# Sonar_Power_Schematic.net
KiCad netlist of a schematic drawn in EAGLE
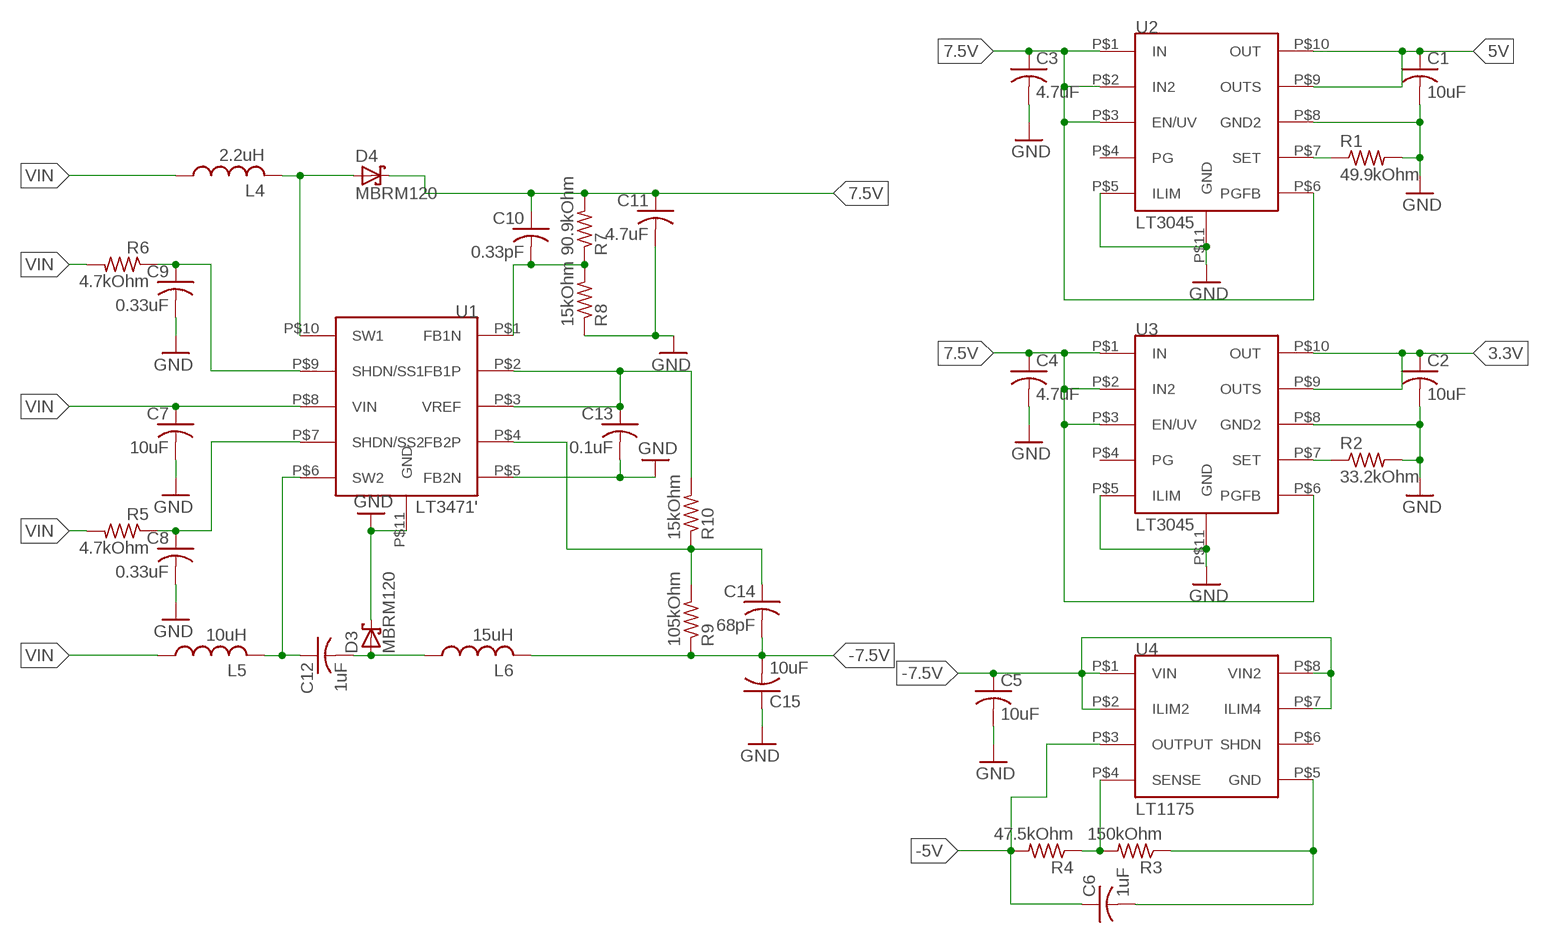
[diagram p0: schematic, sheet 1]

(export (version "E")
  (design (tool "Eeschema 10.0.6"))
  (components
    (comp (ref "C1")
      (value "10uF")
      (footprint "eagle-import:C1206K")
      (libsource (lib "eagle-import") (part "C-USC1206K"))
    )
    (comp (ref "C2")
      (value "10uF")
      (footprint "eagle-import:C1206K")
      (libsource (lib "eagle-import") (part "C-USC1206K"))
    )
    (comp (ref "C3")
      (value "4.7uF")
      (footprint "eagle-import:C0603")
      (libsource (lib "eagle-import") (part "C-USC0603"))
    )
    (comp (ref "C4")
      (value "4.7uF")
      (footprint "eagle-import:C0603")
      (libsource (lib "eagle-import") (part "C-USC0603"))
    )
    (comp (ref "C5")
      (value "10uF")
      (footprint "eagle-import:C0603")
      (libsource (lib "eagle-import") (part "C-USC0603"))
    )
    (comp (ref "C6")
      (value "1uF")
      (footprint "eagle-import:C0603")
      (libsource (lib "eagle-import") (part "C-USC0603"))
    )
    (comp (ref "C7")
      (value "10uF")
      (footprint "eagle-import:C0603")
      (libsource (lib "eagle-import") (part "C-USC0603"))
    )
    (comp (ref "C8")
      (value "0.33uF")
      (footprint "eagle-import:C0603")
      (libsource (lib "eagle-import") (part "C-USC0603"))
    )
    (comp (ref "C9")
      (value "0.33uF")
      (footprint "eagle-import:C0603")
      (libsource (lib "eagle-import") (part "C-USC0603"))
    )
    (comp (ref "C10")
      (value "0.33pF")
      (footprint "eagle-import:C0603")
      (libsource (lib "eagle-import") (part "C-USC0603"))
    )
    (comp (ref "C11")
      (value "4.7uF")
      (footprint "eagle-import:C0603")
      (libsource (lib "eagle-import") (part "C-USC0603"))
    )
    (comp (ref "C12")
      (value "1uF")
      (footprint "eagle-import:C0603")
      (libsource (lib "eagle-import") (part "C-USC0603"))
    )
    (comp (ref "C13")
      (value "0.1uF")
      (footprint "eagle-import:C0603")
      (libsource (lib "eagle-import") (part "C-USC0603"))
    )
    (comp (ref "C14")
      (value "68pF")
      (footprint "eagle-import:C0603")
      (libsource (lib "eagle-import") (part "C-USC0603"))
    )
    (comp (ref "C15")
      (value "10uF")
      (footprint "eagle-import:C0603")
      (libsource (lib "eagle-import") (part "C-USC0603"))
    )
    (comp (ref "D3")
      (value "MBRM120")
      (footprint "eagle-import:DO-216AA")
      (libsource (lib "eagle-import") (part "MBRM120"))
    )
    (comp (ref "D4")
      (value "MBRM120")
      (footprint "eagle-import:DO-216AA")
      (libsource (lib "eagle-import") (part "MBRM120"))
    )
    (comp (ref "L4")
      (value "2.2uH")
      (footprint "eagle-import:NS4.9X4.9")
      (libsource (lib "eagle-import") (part "LQH5BPN2R2N38L"))
    )
    (comp (ref "L5")
      (value "10uH")
      (footprint "eagle-import:NS5X5")
      (libsource (lib "eagle-import") (part "VLS5045EX-100M2"))
    )
    (comp (ref "L6")
      (value "15uH")
      (footprint "eagle-import:NS5X5")
      (libsource (lib "eagle-import") (part "VLS5045EX-150M-CA1"))
    )
    (comp (ref "R1")
      (value "49.9kOhm")
      (footprint "eagle-import:R0603")
      (libsource (lib "eagle-import") (part "R-US_R0603"))
    )
    (comp (ref "R2")
      (value "33.2kOhm")
      (footprint "eagle-import:R0603")
      (libsource (lib "eagle-import") (part "R-US_R0603"))
    )
    (comp (ref "R3")
      (value "150kOhm")
      (footprint "eagle-import:R0603")
      (libsource (lib "eagle-import") (part "R-US_R0603"))
    )
    (comp (ref "R4")
      (value "47.5kOhm")
      (footprint "eagle-import:R0603")
      (libsource (lib "eagle-import") (part "R-US_R0603"))
    )
    (comp (ref "R5")
      (value "4.7kOhm")
      (footprint "eagle-import:R0603")
      (libsource (lib "eagle-import") (part "R-US_R0603"))
    )
    (comp (ref "R6")
      (value "4.7kOhm")
      (footprint "eagle-import:R0603")
      (libsource (lib "eagle-import") (part "R-US_R0603"))
    )
    (comp (ref "R7")
      (value "90.9kOhm")
      (footprint "eagle-import:R0603")
      (libsource (lib "eagle-import") (part "R-US_R0603"))
    )
    (comp (ref "R8")
      (value "15kOhm")
      (footprint "eagle-import:R0603")
      (libsource (lib "eagle-import") (part "R-US_R0603"))
    )
    (comp (ref "R9")
      (value "105kOhm")
      (footprint "eagle-import:R0603")
      (libsource (lib "eagle-import") (part "R-US_R0603"))
    )
    (comp (ref "R10")
      (value "15kOhm")
      (footprint "eagle-import:R0603")
      (libsource (lib "eagle-import") (part "R-US_R0603"))
    )
    (comp (ref "U1")
      (value "LT3471'")
      (footprint "eagle-import:10-WFDFN")
      (libsource (lib "eagle-import") (part "LT3471'"))
    )
    (comp (ref "U2")
      (value "LT3045")
      (footprint "eagle-import:10-WFDFN")
      (libsource (lib "eagle-import") (part "LT3045"))
    )
    (comp (ref "U3")
      (value "LT3045")
      (footprint "eagle-import:10-WFDFN")
      (libsource (lib "eagle-import") (part "LT3045"))
    )
    (comp (ref "U4")
      (value "LT1175")
      (footprint "eagle-import:8-SOIC")
      (libsource (lib "eagle-import") (part "LT1175"))
    )
  )
  (nets
    (net (code "1") (name "-5V") (class "Default")
      (node (ref "C6") (pin "1") (pinfunction "1_1") (pintype "passive"))
      (node (ref "R4") (pin "2") (pinfunction "2_2") (pintype "passive"))
      (node (ref "U4") (pin "P$3") (pinfunction "OUTPUT_P$3") (pintype "bidirectional"))
    )
    (net (code "2") (name "-7.5V") (class "Default")
      (node (ref "C14") (pin "2") (pinfunction "2_2") (pintype "passive"))
      (node (ref "C15") (pin "2") (pinfunction "2_2") (pintype "passive"))
      (node (ref "C5") (pin "1") (pinfunction "1_1") (pintype "passive"))
      (node (ref "L6") (pin "P$2") (pinfunction "2_P$2") (pintype "passive"))
      (node (ref "R9") (pin "1") (pinfunction "1_1") (pintype "passive"))
      (node (ref "U4") (pin "P$1") (pinfunction "VIN_P$1") (pintype "power_in"))
      (node (ref "U4") (pin "P$2") (pinfunction "ILIM2_P$2") (pintype "bidirectional"))
      (node (ref "U4") (pin "P$7") (pinfunction "ILIM4_P$7") (pintype "bidirectional"))
      (node (ref "U4") (pin "P$8") (pinfunction "VIN2_P$8") (pintype "power_in"))
    )
    (net (code "3") (name "3.3V") (class "Default")
      (node (ref "C2") (pin "1") (pinfunction "1_1") (pintype "passive"))
      (node (ref "U3") (pin "P$10") (pinfunction "OUT_P$10") (pintype "bidirectional"))
      (node (ref "U3") (pin "P$9") (pinfunction "OUTS_P$9") (pintype "bidirectional"))
    )
    (net (code "4") (name "5V") (class "Default")
      (node (ref "C1") (pin "1") (pinfunction "1_1") (pintype "passive"))
      (node (ref "U2") (pin "P$10") (pinfunction "OUT_P$10") (pintype "bidirectional"))
      (node (ref "U2") (pin "P$9") (pinfunction "OUTS_P$9") (pintype "bidirectional"))
    )
    (net (code "5") (name "7.5V") (class "Default")
      (node (ref "C10") (pin "1") (pinfunction "1_1") (pintype "passive"))
      (node (ref "C11") (pin "1") (pinfunction "1_1") (pintype "passive"))
      (node (ref "C3") (pin "1") (pinfunction "1_1") (pintype "passive"))
      (node (ref "C4") (pin "1") (pinfunction "1_1") (pintype "passive"))
      (node (ref "D4") (pin "P$1") (pinfunction "C_P$1") (pintype "passive"))
      (node (ref "R7") (pin "2") (pinfunction "2_2") (pintype "passive"))
      (node (ref "U2") (pin "P$1") (pinfunction "IN_P$1") (pintype "power_in"))
      (node (ref "U2") (pin "P$2") (pinfunction "IN2_P$2") (pintype "power_in"))
      (node (ref "U2") (pin "P$3") (pinfunction "EN/UV_P$3") (pintype "bidirectional"))
      (node (ref "U2") (pin "P$6") (pinfunction "PGFB_P$6") (pintype "bidirectional"))
      (node (ref "U3") (pin "P$1") (pinfunction "IN_P$1") (pintype "power_in"))
      (node (ref "U3") (pin "P$2") (pinfunction "IN2_P$2") (pintype "power_in"))
      (node (ref "U3") (pin "P$3") (pinfunction "EN/UV_P$3") (pintype "bidirectional"))
      (node (ref "U3") (pin "P$6") (pinfunction "PGFB_P$6") (pintype "bidirectional"))
    )
    (net (code "6") (name "GND") (class "Default")
      (node (ref "C1") (pin "2") (pinfunction "2_2") (pintype "passive"))
      (node (ref "C11") (pin "2") (pinfunction "2_2") (pintype "passive"))
      (node (ref "C13") (pin "2") (pinfunction "2_2") (pintype "passive"))
      (node (ref "C15") (pin "1") (pinfunction "1_1") (pintype "passive"))
      (node (ref "C2") (pin "2") (pinfunction "2_2") (pintype "passive"))
      (node (ref "C3") (pin "2") (pinfunction "2_2") (pintype "passive"))
      (node (ref "C4") (pin "2") (pinfunction "2_2") (pintype "passive"))
      (node (ref "C5") (pin "2") (pinfunction "2_2") (pintype "passive"))
      (node (ref "C7") (pin "2") (pinfunction "2_2") (pintype "passive"))
      (node (ref "C8") (pin "2") (pinfunction "2_2") (pintype "passive"))
      (node (ref "C9") (pin "2") (pinfunction "2_2") (pintype "passive"))
      (node (ref "D3") (pin "P$1") (pinfunction "C_P$1") (pintype "passive"))
      (node (ref "R1") (pin "2") (pinfunction "2_2") (pintype "passive"))
      (node (ref "R2") (pin "2") (pinfunction "2_2") (pintype "passive"))
      (node (ref "R8") (pin "1") (pinfunction "1_1") (pintype "passive"))
      (node (ref "U1") (pin "P$11") (pinfunction "GND_P$11") (pintype "power_in"))
      (node (ref "U1") (pin "P$5") (pinfunction "FB2N_P$5") (pintype "bidirectional"))
      (node (ref "U2") (pin "P$11") (pinfunction "GND_P$11") (pintype "power_in"))
      (node (ref "U2") (pin "P$5") (pinfunction "ILIM_P$5") (pintype "bidirectional"))
      (node (ref "U2") (pin "P$8") (pinfunction "GND2_P$8") (pintype "power_in"))
      (node (ref "U3") (pin "P$11") (pinfunction "GND_P$11") (pintype "power_in"))
      (node (ref "U3") (pin "P$5") (pinfunction "ILIM_P$5") (pintype "bidirectional"))
      (node (ref "U3") (pin "P$8") (pinfunction "GND2_P$8") (pintype "power_in"))
    )
    (net (code "7") (name "Net-(D3-A)") (class "Default")
      (node (ref "C12") (pin "2") (pinfunction "2_2") (pintype "passive"))
      (node (ref "D3") (pin "P$2") (pinfunction "A_P$2") (pintype "passive"))
      (node (ref "L6") (pin "P$1") (pinfunction "1_P$1") (pintype "passive"))
    )
    (net (code "8") (name "Net-(D4-A)") (class "Default")
      (node (ref "D4") (pin "P$2") (pinfunction "A_P$2") (pintype "passive"))
      (node (ref "L4") (pin "P$2") (pinfunction "2_P$2") (pintype "passive"))
      (node (ref "U1") (pin "P$10") (pinfunction "SW1_P$10") (pintype "bidirectional"))
    )
    (net (code "9") (name "Net-(L5-2)") (class "Default")
      (node (ref "C12") (pin "1") (pinfunction "1_1") (pintype "passive"))
      (node (ref "L5") (pin "P$2") (pinfunction "2_P$2") (pintype "passive"))
      (node (ref "U1") (pin "P$6") (pinfunction "SW2_P$6") (pintype "bidirectional"))
    )
    (net (code "10") (name "Net-(U1-FB1N)") (class "Default")
      (node (ref "C10") (pin "2") (pinfunction "2_2") (pintype "passive"))
      (node (ref "R7") (pin "1") (pinfunction "1_1") (pintype "passive"))
      (node (ref "R8") (pin "2") (pinfunction "2_2") (pintype "passive"))
      (node (ref "U1") (pin "P$1") (pinfunction "FB1N_P$1") (pintype "bidirectional"))
    )
    (net (code "11") (name "Net-(U1-FB1P)") (class "Default")
      (node (ref "C13") (pin "1") (pinfunction "1_1") (pintype "passive"))
      (node (ref "R10") (pin "2") (pinfunction "2_2") (pintype "passive"))
      (node (ref "U1") (pin "P$2") (pinfunction "FB1P_P$2") (pintype "bidirectional"))
      (node (ref "U1") (pin "P$3") (pinfunction "VREF_P$3") (pintype "power_in"))
    )
    (net (code "12") (name "Net-(U1-FB2P)") (class "Default")
      (node (ref "C14") (pin "1") (pinfunction "1_1") (pintype "passive"))
      (node (ref "R10") (pin "1") (pinfunction "1_1") (pintype "passive"))
      (node (ref "R9") (pin "2") (pinfunction "2_2") (pintype "passive"))
      (node (ref "U1") (pin "P$4") (pinfunction "FB2P_P$4") (pintype "bidirectional"))
    )
    (net (code "13") (name "Net-(U1-SHDN{slash}SS1)") (class "Default")
      (node (ref "C9") (pin "1") (pinfunction "1_1") (pintype "passive"))
      (node (ref "R6") (pin "1") (pinfunction "1_1") (pintype "passive"))
      (node (ref "U1") (pin "P$9") (pinfunction "SHDN/SS1_P$9") (pintype "bidirectional"))
    )
    (net (code "14") (name "Net-(U1-SHDN{slash}SS2)") (class "Default")
      (node (ref "C8") (pin "1") (pinfunction "1_1") (pintype "passive"))
      (node (ref "R5") (pin "1") (pinfunction "1_1") (pintype "passive"))
      (node (ref "U1") (pin "P$7") (pinfunction "SHDN/SS2_P$7") (pintype "bidirectional"))
    )
    (net (code "15") (name "Net-(U2-SET)") (class "Default")
      (node (ref "R1") (pin "1") (pinfunction "1_1") (pintype "passive"))
      (node (ref "U2") (pin "P$7") (pinfunction "SET_P$7") (pintype "bidirectional"))
    )
    (net (code "16") (name "Net-(U3-SET)") (class "Default")
      (node (ref "R2") (pin "1") (pinfunction "1_1") (pintype "passive"))
      (node (ref "U3") (pin "P$7") (pinfunction "SET_P$7") (pintype "bidirectional"))
    )
    (net (code "17") (name "Net-(U4-GND)") (class "Default")
      (node (ref "C6") (pin "2") (pinfunction "2_2") (pintype "passive"))
      (node (ref "R3") (pin "1") (pinfunction "1_1") (pintype "passive"))
      (node (ref "U4") (pin "P$5") (pinfunction "GND_P$5") (pintype "power_in"))
    )
    (net (code "18") (name "Net-(U4-SENSE)") (class "Default")
      (node (ref "R3") (pin "2") (pinfunction "2_2") (pintype "passive"))
      (node (ref "R4") (pin "1") (pinfunction "1_1") (pintype "passive"))
      (node (ref "U4") (pin "P$4") (pinfunction "SENSE_P$4") (pintype "bidirectional"))
    )
    (net (code "19") (name "VIN") (class "Default")
      (node (ref "C7") (pin "1") (pinfunction "1_1") (pintype "passive"))
      (node (ref "L4") (pin "P$1") (pinfunction "1_P$1") (pintype "passive"))
      (node (ref "L5") (pin "P$1") (pinfunction "1_P$1") (pintype "passive"))
      (node (ref "R5") (pin "2") (pinfunction "2_2") (pintype "passive"))
      (node (ref "R6") (pin "2") (pinfunction "2_2") (pintype "passive"))
      (node (ref "U1") (pin "P$8") (pinfunction "VIN_P$8") (pintype "power_in"))
    )
    (net (code "20") (name "unconnected-(U2-PG-PadP$4)") (class "Default")
      (node (ref "U2") (pin "P$4") (pinfunction "PG_P$4") (pintype "bidirectional"))
    )
    (net (code "21") (name "unconnected-(U3-PG-PadP$4)") (class "Default")
      (node (ref "U3") (pin "P$4") (pinfunction "PG_P$4") (pintype "bidirectional"))
    )
    (net (code "22") (name "unconnected-(U4-SHDN-PadP$6)") (class "Default")
      (node (ref "U4") (pin "P$6") (pinfunction "SHDN_P$6") (pintype "bidirectional"))
    )
  )
)
